# icyradio-exp-fan.net
KiCad netlist of a schematic drawn in EAGLE
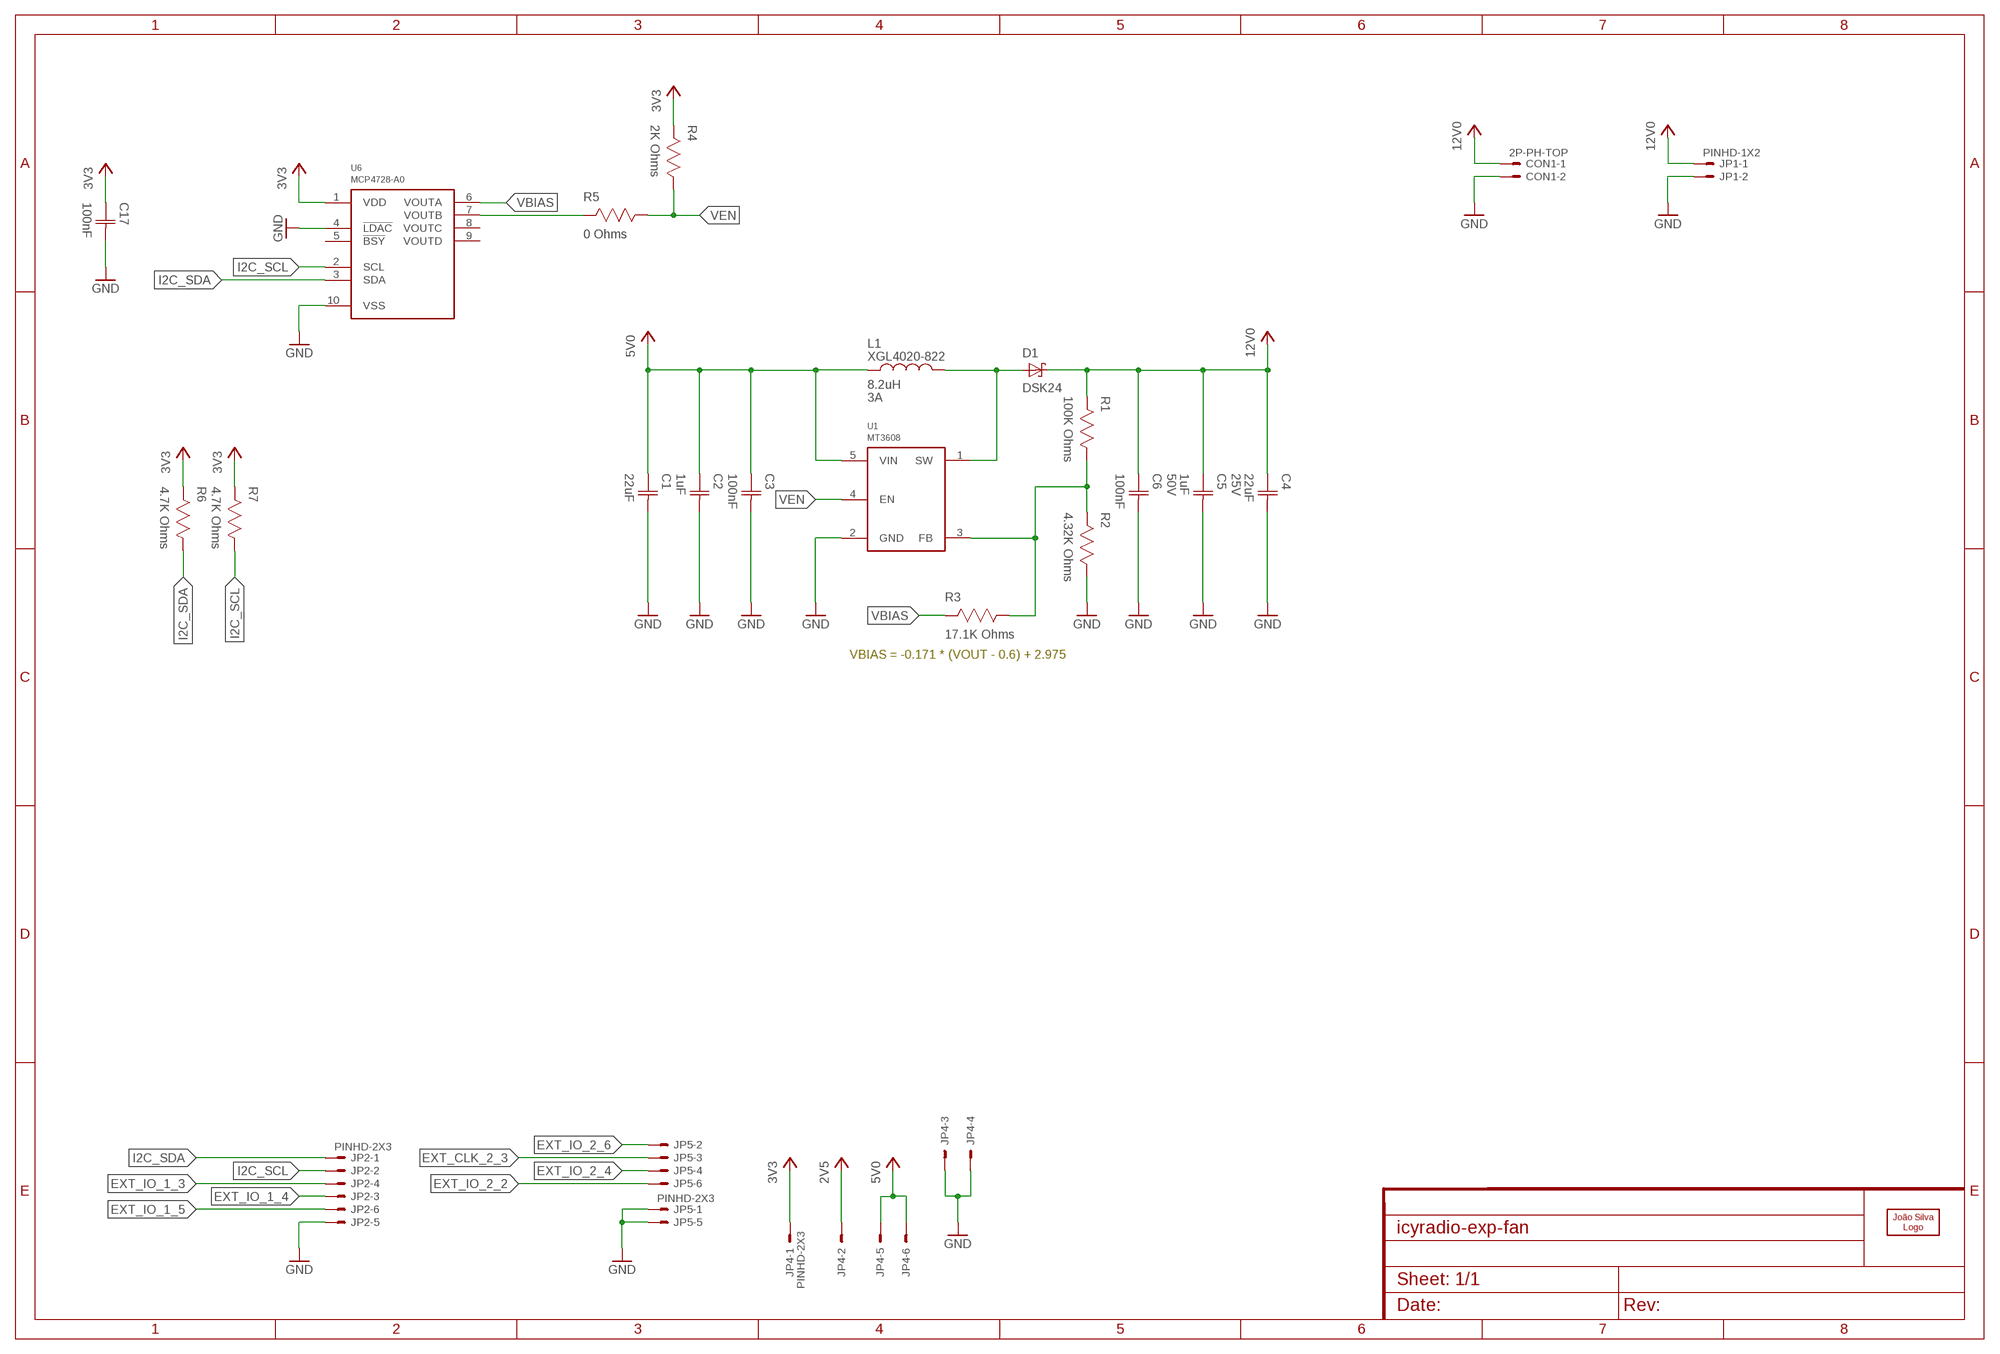
[diagram p0: schematic, sheet 1]

(export (version "E")
  (design (tool "Eeschema 10.0.6"))
  (components
    (comp (ref "C1")
      (value "22uF")
      (footprint "eagle-import:CAP1206")
      (libsource (lib "eagle-import") (part "CAPACITOR-1206"))
    )
    (comp (ref "C2")
      (value "1uF")
      (footprint "eagle-import:CAP0402")
      (libsource (lib "eagle-import") (part "CAPACITOR-0402"))
    )
    (comp (ref "C3")
      (value "100nF")
      (footprint "eagle-import:CAP0402")
      (libsource (lib "eagle-import") (part "CAPACITOR-0402"))
    )
    (comp (ref "C4")
      (value "22uF")
      (footprint "eagle-import:CAP1206")
      (fields (field (name "VOLTAGE") "25V"))
      (libsource (lib "eagle-import") (part "CAPACITOR-1206"))
    )
    (comp (ref "C5")
      (value "1uF")
      (footprint "eagle-import:CAP0402")
      (fields (field (name "VOLTAGE") "50V"))
      (libsource (lib "eagle-import") (part "CAPACITOR-0402"))
    )
    (comp (ref "C6")
      (value "100nF")
      (footprint "eagle-import:CAP0402")
      (libsource (lib "eagle-import") (part "CAPACITOR-0402"))
    )
    (comp (ref "C17")
      (value "100nF")
      (footprint "eagle-import:CAP0402")
      (libsource (lib "eagle-import") (part "CAPACITOR-0402"))
    )
    (comp (ref "CON1")
      (value "2P-PH-TOP")
      (footprint "eagle-import:PH-02-TOP")
      (libsource (lib "eagle-import") (part "2P-PH-TOP"))
    )
    (comp (ref "D1")
      (value "DSK24")
      (footprint "eagle-import:SOD-123F")
      (libsource (lib "eagle-import") (part "DSK24"))
    )
    (comp (ref "JP1")
      (value "PINHD-1X2")
      (footprint "eagle-import:1X02")
      (libsource (lib "eagle-import") (part "PINHD-1X2"))
    )
    (comp (ref "JP2")
      (value "PINHD-2X3")
      (footprint "eagle-import:2X03")
      (libsource (lib "eagle-import") (part "PINHD-2X3"))
    )
    (comp (ref "JP4")
      (value "PINHD-2X3")
      (footprint "eagle-import:2X03")
      (libsource (lib "eagle-import") (part "PINHD-2X3"))
    )
    (comp (ref "JP5")
      (value "PINHD-2X3")
      (footprint "eagle-import:2X03")
      (libsource (lib "eagle-import") (part "PINHD-2X3"))
    )
    (comp (ref "L1")
      (value "8.2uH")
      (footprint "eagle-import:XGL4020")
      (fields (field (name "CURRENT") "3A") (field (name "REF") "XGL4020-822"))
      (libsource (lib "eagle-import") (part "XGL4020-822"))
    )
    (comp (ref "LOGO1")
      (value "JSILVA-10MM")
      (footprint "eagle-import:JSILVA_10MM")
      (libsource (lib "eagle-import") (part "JSILVA-10MM"))
    )
    (comp (ref "R1")
      (value "100K Ohms")
      (footprint "eagle-import:RES0402")
      (libsource (lib "eagle-import") (part "RESISTOR-0402"))
    )
    (comp (ref "R2")
      (value "4.32K Ohms")
      (footprint "eagle-import:RES0402")
      (libsource (lib "eagle-import") (part "RESISTOR-0402"))
    )
    (comp (ref "R3")
      (value "17.1K Ohms")
      (footprint "eagle-import:RES0402")
      (libsource (lib "eagle-import") (part "RESISTOR-0402"))
    )
    (comp (ref "R4")
      (value "2K Ohms")
      (footprint "eagle-import:RES0402")
      (libsource (lib "eagle-import") (part "RESISTOR-0402"))
    )
    (comp (ref "R5")
      (value "0 Ohms")
      (footprint "eagle-import:RES0402")
      (libsource (lib "eagle-import") (part "RESISTOR-0402"))
    )
    (comp (ref "R6")
      (value "4.7K Ohms")
      (footprint "eagle-import:RES0402")
      (libsource (lib "eagle-import") (part "RESISTOR-0402"))
    )
    (comp (ref "R7")
      (value "4.7K Ohms")
      (footprint "eagle-import:RES0402")
      (libsource (lib "eagle-import") (part "RESISTOR-0402"))
    )
    (comp (ref "U1")
      (value "MT3608")
      (footprint "eagle-import:SOT23-6")
      (libsource (lib "eagle-import") (part "MT3608"))
    )
    (comp (ref "U6")
      (value "MCP4728-A0")
      (footprint "eagle-import:MSOP10")
      (libsource (lib "eagle-import") (part "MCP4728-A0"))
    )
  )
  (nets
    (net (code "1") (name "2V5") (class "Default")
      (node (ref "JP4") (pin "2") (pinfunction "S_2") (pintype "passive"))
    )
    (net (code "2") (name "3V3") (class "Default")
      (node (ref "C17") (pin "1") (pinfunction "C1_1") (pintype "passive"))
      (node (ref "JP4") (pin "1") (pinfunction "S_1") (pintype "passive"))
      (node (ref "R4") (pin "2") (pinfunction "2_2") (pintype "passive"))
      (node (ref "R6") (pin "2") (pinfunction "2_2") (pintype "passive"))
      (node (ref "R7") (pin "2") (pinfunction "2_2") (pintype "passive"))
      (node (ref "U6") (pin "1") (pinfunction "VDD_1") (pintype "bidirectional"))
    )
    (net (code "3") (name "5V0") (class "Default")
      (node (ref "C1") (pin "1") (pinfunction "C1_1") (pintype "passive"))
      (node (ref "C2") (pin "1") (pinfunction "C1_1") (pintype "passive"))
      (node (ref "C3") (pin "1") (pinfunction "C1_1") (pintype "passive"))
      (node (ref "JP4") (pin "5") (pinfunction "S_5") (pintype "passive"))
      (node (ref "JP4") (pin "6") (pinfunction "S_6") (pintype "passive"))
      (node (ref "L1") (pin "1") (pinfunction "1_1") (pintype "passive"))
      (node (ref "U1") (pin "5") (pinfunction "VIN_5") (pintype "bidirectional"))
    )
    (net (code "4") (name "12V0") (class "Default")
      (node (ref "C4") (pin "1") (pinfunction "C1_1") (pintype "passive"))
      (node (ref "C5") (pin "1") (pinfunction "C1_1") (pintype "passive"))
      (node (ref "C6") (pin "1") (pinfunction "C1_1") (pintype "passive"))
      (node (ref "CON1") (pin "1") (pinfunction "S_1") (pintype "passive"))
      (node (ref "D1") (pin "C") (pinfunction "C_C") (pintype "passive"))
      (node (ref "JP1") (pin "1") (pinfunction "S_1") (pintype "passive"))
      (node (ref "R1") (pin "2") (pinfunction "2_2") (pintype "passive"))
    )
    (net (code "5") (name "EXT_CLK_2_3") (class "Default")
      (node (ref "JP5") (pin "3") (pinfunction "S_3") (pintype "passive"))
    )
    (net (code "6") (name "EXT_IO_1_3") (class "Default")
      (node (ref "JP2") (pin "4") (pinfunction "S_4") (pintype "passive"))
    )
    (net (code "7") (name "EXT_IO_1_4") (class "Default")
      (node (ref "JP2") (pin "3") (pinfunction "S_3") (pintype "passive"))
    )
    (net (code "8") (name "EXT_IO_1_5") (class "Default")
      (node (ref "JP2") (pin "6") (pinfunction "S_6") (pintype "passive"))
    )
    (net (code "9") (name "EXT_IO_2_2") (class "Default")
      (node (ref "JP5") (pin "6") (pinfunction "S_6") (pintype "passive"))
    )
    (net (code "10") (name "EXT_IO_2_4") (class "Default")
      (node (ref "JP5") (pin "4") (pinfunction "S_4") (pintype "passive"))
    )
    (net (code "11") (name "EXT_IO_2_6") (class "Default")
      (node (ref "JP5") (pin "2") (pinfunction "S_2") (pintype "passive"))
    )
    (net (code "12") (name "GND") (class "Default")
      (node (ref "C1") (pin "2") (pinfunction "C2_2") (pintype "passive"))
      (node (ref "C17") (pin "2") (pinfunction "C2_2") (pintype "passive"))
      (node (ref "C2") (pin "2") (pinfunction "C2_2") (pintype "passive"))
      (node (ref "C3") (pin "2") (pinfunction "C2_2") (pintype "passive"))
      (node (ref "C4") (pin "2") (pinfunction "C2_2") (pintype "passive"))
      (node (ref "C5") (pin "2") (pinfunction "C2_2") (pintype "passive"))
      (node (ref "C6") (pin "2") (pinfunction "C2_2") (pintype "passive"))
      (node (ref "CON1") (pin "2") (pinfunction "S_2") (pintype "passive"))
      (node (ref "JP1") (pin "2") (pinfunction "S_2") (pintype "passive"))
      (node (ref "JP2") (pin "5") (pinfunction "S_5") (pintype "passive"))
      (node (ref "JP4") (pin "3") (pinfunction "S_3") (pintype "passive"))
      (node (ref "JP4") (pin "4") (pinfunction "S_4") (pintype "passive"))
      (node (ref "JP5") (pin "1") (pinfunction "S_1") (pintype "passive"))
      (node (ref "JP5") (pin "5") (pinfunction "S_5") (pintype "passive"))
      (node (ref "R2") (pin "1") (pinfunction "1_1") (pintype "passive"))
      (node (ref "U1") (pin "2") (pinfunction "GND_2") (pintype "bidirectional"))
      (node (ref "U6") (pin "10") (pinfunction "VSS_10") (pintype "bidirectional"))
      (node (ref "U6") (pin "4") (pinfunction "~{LDAC}_4") (pintype "bidirectional"))
    )
    (net (code "13") (name "I2C_SCL") (class "Default")
      (node (ref "JP2") (pin "2") (pinfunction "S_2") (pintype "passive"))
      (node (ref "R7") (pin "1") (pinfunction "1_1") (pintype "passive"))
      (node (ref "U6") (pin "2") (pinfunction "SCL_2") (pintype "bidirectional"))
    )
    (net (code "14") (name "I2C_SDA") (class "Default")
      (node (ref "JP2") (pin "1") (pinfunction "S_1") (pintype "passive"))
      (node (ref "R6") (pin "1") (pinfunction "1_1") (pintype "passive"))
      (node (ref "U6") (pin "3") (pinfunction "SDA_3") (pintype "bidirectional"))
    )
    (net (code "15") (name "Net-(U1-FB)") (class "Default")
      (node (ref "R1") (pin "1") (pinfunction "1_1") (pintype "passive"))
      (node (ref "R2") (pin "2") (pinfunction "2_2") (pintype "passive"))
      (node (ref "R3") (pin "1") (pinfunction "1_1") (pintype "passive"))
      (node (ref "U1") (pin "3") (pinfunction "FB_3") (pintype "bidirectional"))
    )
    (net (code "16") (name "Net-(U1-SW)") (class "Default")
      (node (ref "D1") (pin "A") (pinfunction "A_A") (pintype "passive"))
      (node (ref "L1") (pin "2") (pinfunction "2_2") (pintype "passive"))
      (node (ref "U1") (pin "1") (pinfunction "SW_1") (pintype "bidirectional"))
    )
    (net (code "17") (name "Net-(U6-VOUTB)") (class "Default")
      (node (ref "R5") (pin "2") (pinfunction "2_2") (pintype "passive"))
      (node (ref "U6") (pin "7") (pinfunction "VOUTB_7") (pintype "bidirectional"))
    )
    (net (code "18") (name "VBIAS") (class "Default")
      (node (ref "R3") (pin "2") (pinfunction "2_2") (pintype "passive"))
      (node (ref "U6") (pin "6") (pinfunction "VOUTA_6") (pintype "bidirectional"))
    )
    (net (code "19") (name "VEN") (class "Default")
      (node (ref "R4") (pin "1") (pinfunction "1_1") (pintype "passive"))
      (node (ref "R5") (pin "1") (pinfunction "1_1") (pintype "passive"))
      (node (ref "U1") (pin "4") (pinfunction "EN_4") (pintype "bidirectional"))
    )
    (net (code "20") (name "unconnected-(U6-VOUTC-Pad8)") (class "Default")
      (node (ref "U6") (pin "8") (pinfunction "VOUTC_8") (pintype "bidirectional"))
    )
    (net (code "21") (name "unconnected-(U6-VOUTD-Pad9)") (class "Default")
      (node (ref "U6") (pin "9") (pinfunction "VOUTD_9") (pintype "bidirectional"))
    )
    (net (code "22") (name "unconnected-(U6-~{BSY}-Pad5)") (class "Default")
      (node (ref "U6") (pin "5") (pinfunction "~{BSY}_5") (pintype "bidirectional"))
    )
  )
)
